# 1-Schematic_ESP32_expandable_board.net
KiCad netlist of a schematic drawn in EasyEDA
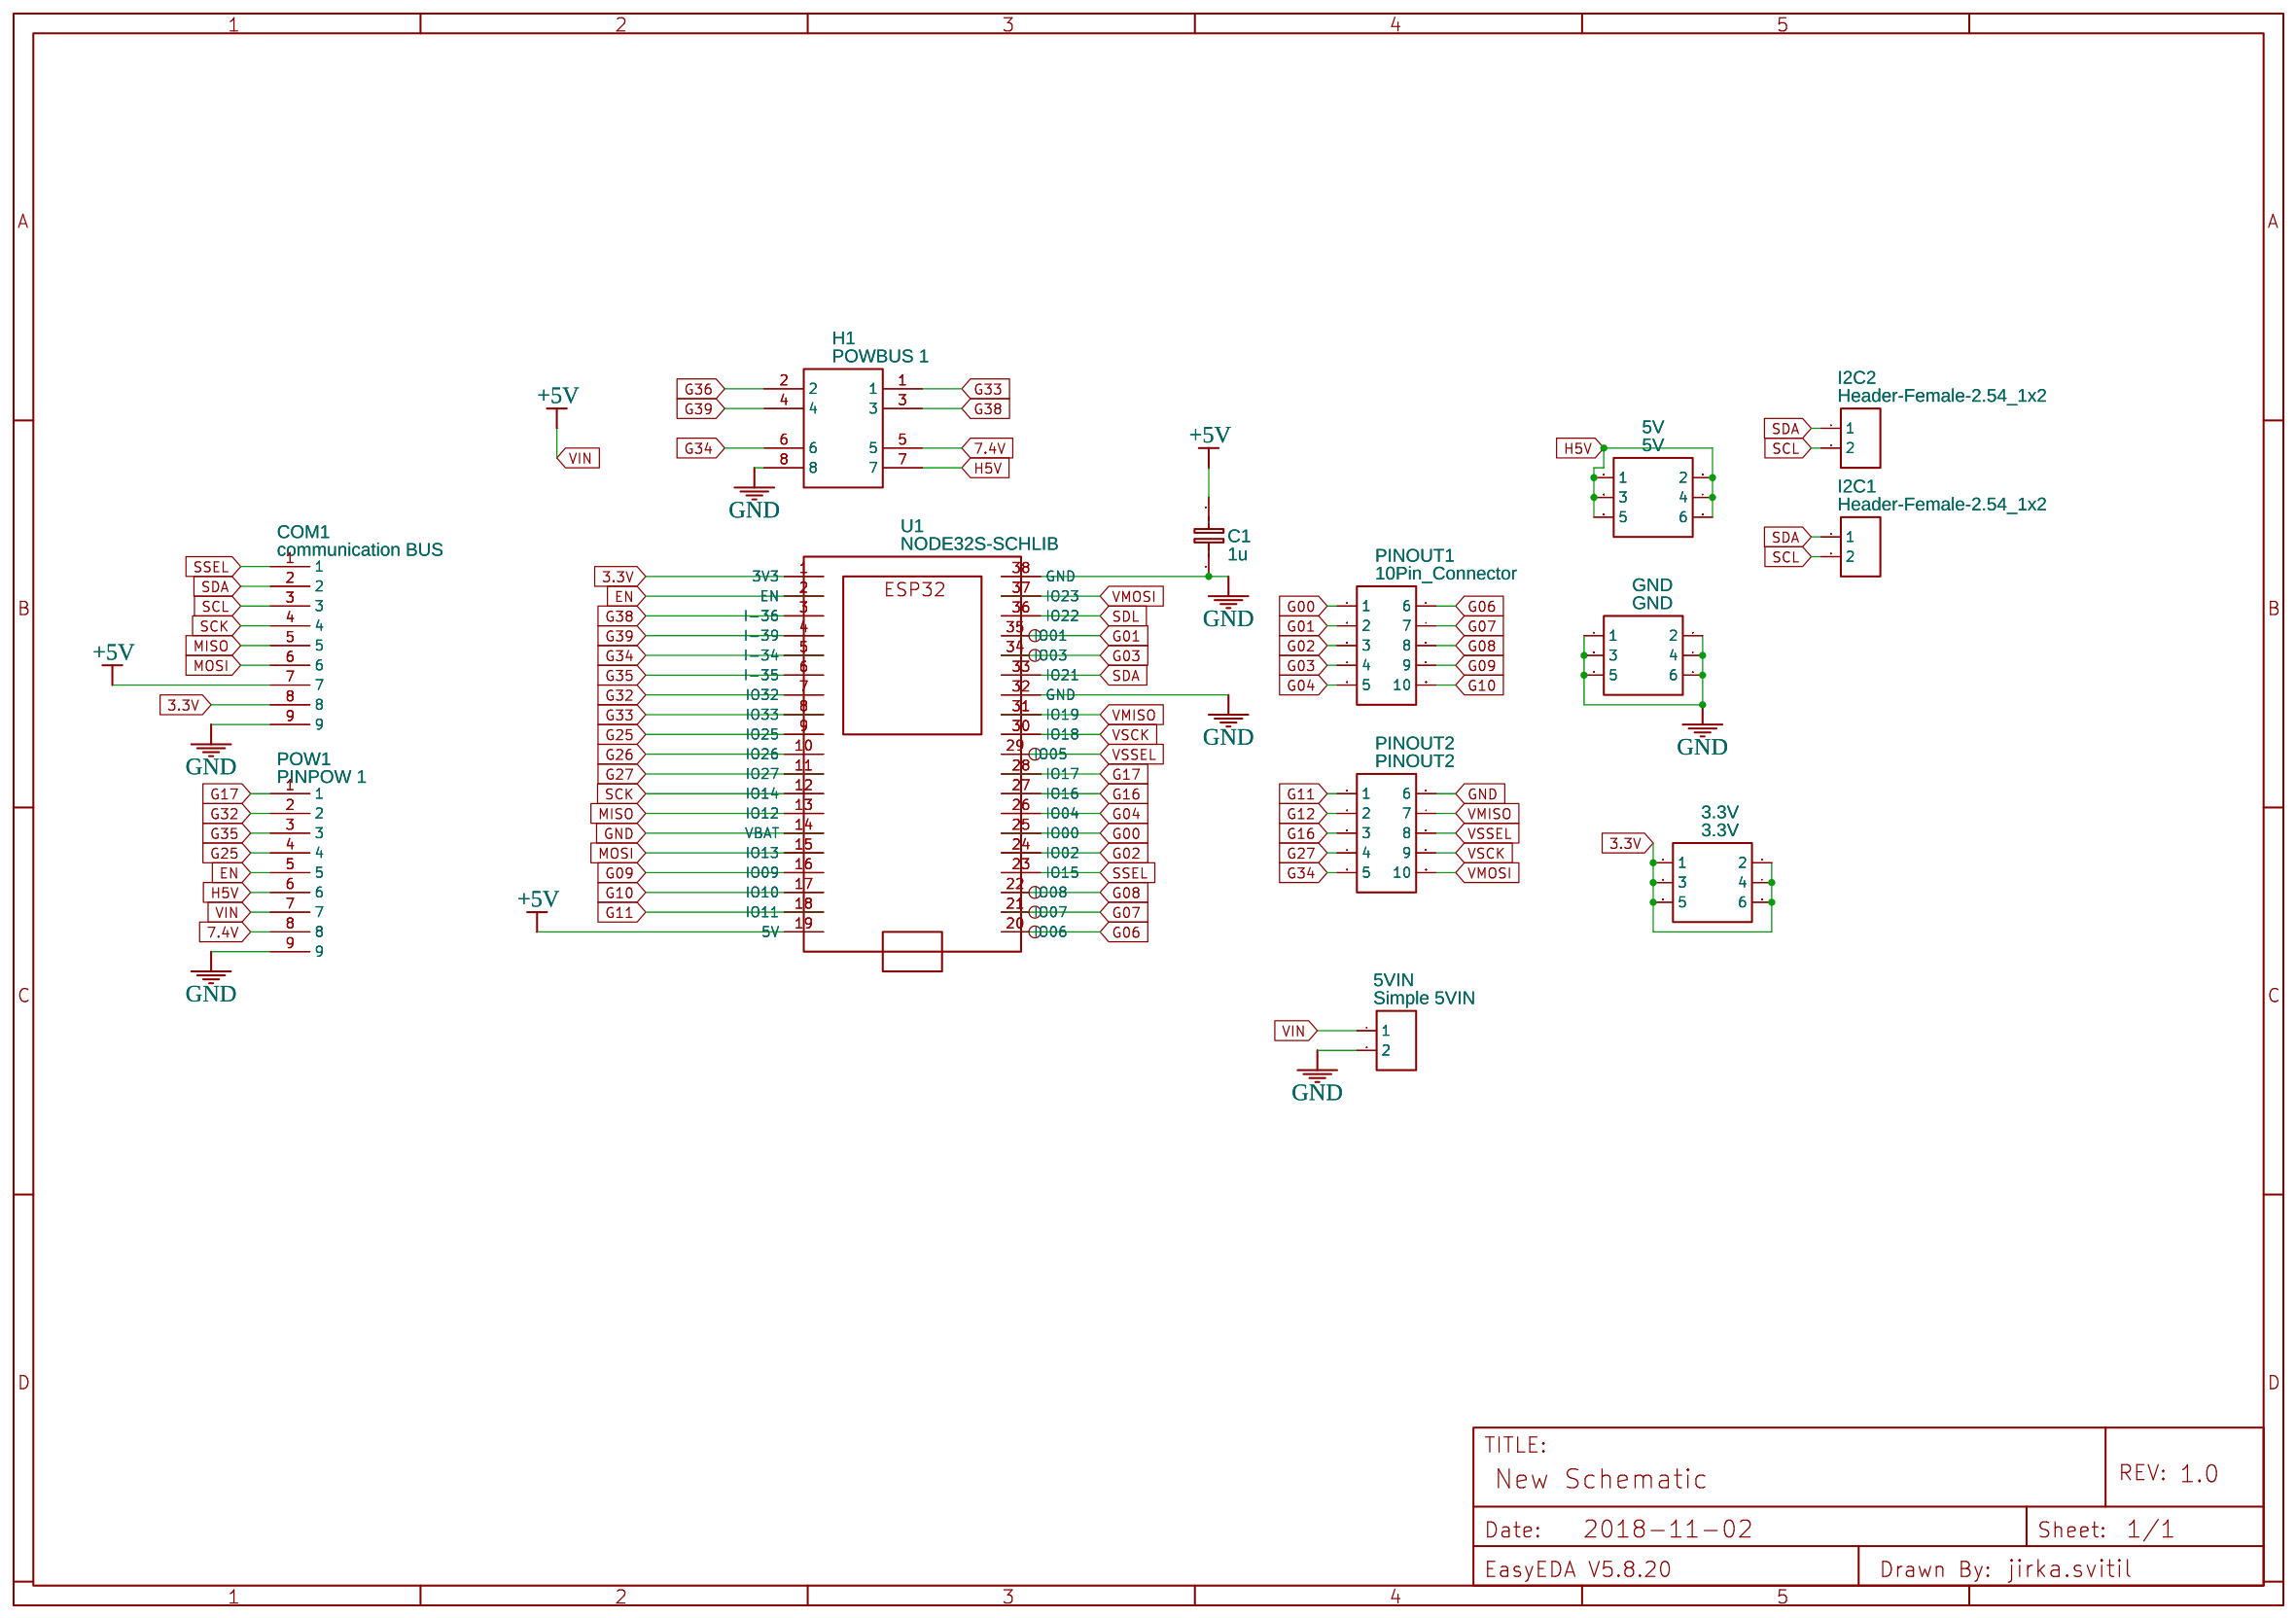
[diagram p0: schematic sheet]

(export (version "E")
  (design (tool "Eeschema 10.0.6"))
  (components
    (comp (ref "3.3V")
      (value "3.3V")
      (fields
        (field (name "BOM_Manufacturer Part") "2X3 2.54mm IDC Box")
        (field (name "BOM_Supplier Part") "C11214")
      )
      (libsource (lib "") (part "Unknown_860_440"))
    )
    (comp (ref "5V")
      (value "5V")
      (fields
        (field (name "BOM_Manufacturer Part") "2X3 2.54mm IDC Box")
        (field (name "BOM_Supplier Part") "C11214")
      )
      (libsource (lib "") (part "Unknown_830_245"))
    )
    (comp (ref "5VIN")
      (value "Simple 5VIN")
      (fields
        (field (name "BOM_Manufacturer Part") "2.54-1*2PFemale")
        (field (name "BOM_Supplier Part") "C49661")
      )
      (libsource (lib "") (part "Unknown_695_520"))
    )
    (comp (ref "C1")
      (value "1u")
      (fields (field (name "BOM_Manufacturer Part") "?"))
      (libsource (lib "") (part "Cap_RAD-0.1_EU"))
    )
    (comp (ref "COM1")
      (value "communication BUS")
      (fields (field (name "BOM_Manufacturer Part") "?"))
      (libsource (lib "") (part "Unknown_160_270"))
    )
    (comp (ref "GND")
      (value "GND")
      (fields
        (field (name "BOM_Manufacturer Part") "2X3 2.54mm IDC Box")
        (field (name "BOM_Supplier Part") "C11214")
      )
      (libsource (lib "") (part "Unknown_825_325"))
    )
    (comp (ref "H1")
      (value "POWBUS 1")
      (fields (field (name "BOM_Manufacturer Part") "Header 4x2"))
      (libsource (lib "") (part "Unknown_420_210"))
    )
    (comp (ref "I2C1")
      (value "Header-Female-2.54_1x2")
      (fields
        (field (name "BOM_Manufacturer Part") "2.54-1*2PFemale")
        (field (name "BOM_Supplier Part") "C49661")
      )
      (libsource (lib "") (part "Unknown_930_270"))
    )
    (comp (ref "I2C2")
      (value "Header-Female-2.54_1x2")
      (fields
        (field (name "BOM_Manufacturer Part") "2.54-1*2PFemale")
        (field (name "BOM_Supplier Part") "C49661")
      )
      (libsource (lib "") (part "Unknown_930_215"))
    )
    (comp (ref "PINOUT1")
      (value "10Pin_Connector")
      (fields (field (name "BOM_Manufacturer Part") "?"))
      (libsource (lib "") (part "Unknown_670_290"))
    )
    (comp (ref "PINOUT2")
      (value "PINOUT2")
      (fields (field (name "BOM_Manufacturer Part") "?"))
      (libsource (lib "") (part "Unknown_670_385"))
    )
    (comp (ref "POW1")
      (value "PINPOW 1")
      (fields (field (name "BOM_Manufacturer Part") "?"))
      (libsource (lib "") (part "Unknown_160_385"))
    )
    (comp (ref "U1")
      (value "NODE32S-SCHLIB")
      (fields (field (name "BOM_Manufacturer Part") "New SchematicLib"))
      (libsource (lib "") (part "Unknown_400_275"))
    )
  )
  (nets
    (net (code "1") (name "3.3V") (class "Default")
      (node (ref "3.3V") (pin "1") (pinfunction "1_1") (pintype "unspecified"))
      (node (ref "3.3V") (pin "2") (pinfunction "2_2") (pintype "unspecified"))
      (node (ref "3.3V") (pin "3") (pinfunction "3_3") (pintype "unspecified"))
      (node (ref "3.3V") (pin "4") (pinfunction "4_4") (pintype "unspecified"))
      (node (ref "3.3V") (pin "5") (pinfunction "5_5") (pintype "unspecified"))
      (node (ref "3.3V") (pin "6") (pinfunction "6_6") (pintype "unspecified"))
      (node (ref "COM1") (pin "8") (pinfunction "8_8") (pintype "unspecified"))
      (node (ref "U1") (pin "1") (pinfunction "3V3_1") (pintype "unspecified"))
    )
    (net (code "2") (name "7.4V") (class "Default")
      (node (ref "H1") (pin "5") (pinfunction "5_5") (pintype "unspecified"))
      (node (ref "POW1") (pin "8") (pinfunction "8_8") (pintype "unspecified"))
    )
    (net (code "3") (name "EN") (class "Default")
      (node (ref "POW1") (pin "5") (pinfunction "5_5") (pintype "unspecified"))
      (node (ref "U1") (pin "2") (pinfunction "EN_2") (pintype "unspecified"))
    )
    (net (code "4") (name "G00") (class "Default")
      (node (ref "PINOUT1") (pin "1") (pinfunction "1_1") (pintype "unspecified"))
      (node (ref "U1") (pin "25") (pinfunction "IO00_25") (pintype "unspecified"))
    )
    (net (code "5") (name "G01") (class "Default")
      (node (ref "PINOUT1") (pin "2") (pinfunction "2_2") (pintype "unspecified"))
      (node (ref "U1") (pin "35") (pinfunction "IO01_35") (pintype "unspecified"))
    )
    (net (code "6") (name "G02") (class "Default")
      (node (ref "PINOUT1") (pin "3") (pinfunction "3_3") (pintype "unspecified"))
      (node (ref "U1") (pin "24") (pinfunction "IO02_24") (pintype "unspecified"))
    )
    (net (code "7") (name "G03") (class "Default")
      (node (ref "PINOUT1") (pin "4") (pinfunction "4_4") (pintype "unspecified"))
      (node (ref "U1") (pin "34") (pinfunction "IO03_34") (pintype "unspecified"))
    )
    (net (code "8") (name "G04") (class "Default")
      (node (ref "PINOUT1") (pin "5") (pinfunction "5_5") (pintype "unspecified"))
      (node (ref "U1") (pin "26") (pinfunction "IO04_26") (pintype "unspecified"))
    )
    (net (code "9") (name "G06") (class "Default")
      (node (ref "PINOUT1") (pin "6") (pinfunction "6_6") (pintype "unspecified"))
      (node (ref "U1") (pin "20") (pinfunction "IO06_20") (pintype "unspecified"))
    )
    (net (code "10") (name "G07") (class "Default")
      (node (ref "PINOUT1") (pin "7") (pinfunction "7_7") (pintype "unspecified"))
      (node (ref "U1") (pin "21") (pinfunction "IO07_21") (pintype "unspecified"))
    )
    (net (code "11") (name "G08") (class "Default")
      (node (ref "PINOUT1") (pin "8") (pinfunction "8_8") (pintype "unspecified"))
      (node (ref "U1") (pin "22") (pinfunction "IO08_22") (pintype "unspecified"))
    )
    (net (code "12") (name "G09") (class "Default")
      (node (ref "PINOUT1") (pin "9") (pinfunction "9_9") (pintype "unspecified"))
      (node (ref "U1") (pin "16") (pinfunction "IO09_16") (pintype "unspecified"))
    )
    (net (code "13") (name "G10") (class "Default")
      (node (ref "PINOUT1") (pin "10") (pinfunction "10_10") (pintype "unspecified"))
      (node (ref "U1") (pin "17") (pinfunction "IO10_17") (pintype "unspecified"))
    )
    (net (code "14") (name "G11") (class "Default")
      (node (ref "PINOUT2") (pin "1") (pinfunction "1_1") (pintype "unspecified"))
      (node (ref "U1") (pin "18") (pinfunction "IO11_18") (pintype "unspecified"))
    )
    (net (code "15") (name "G12") (class "Default")
      (node (ref "PINOUT2") (pin "2") (pinfunction "2_2") (pintype "unspecified"))
    )
    (net (code "16") (name "G16") (class "Default")
      (node (ref "PINOUT2") (pin "3") (pinfunction "3_3") (pintype "unspecified"))
      (node (ref "U1") (pin "27") (pinfunction "IO16_27") (pintype "unspecified"))
    )
    (net (code "17") (name "G17") (class "Default")
      (node (ref "POW1") (pin "1") (pinfunction "1_1") (pintype "unspecified"))
      (node (ref "U1") (pin "28") (pinfunction "IO17_28") (pintype "unspecified"))
    )
    (net (code "18") (name "G25") (class "Default")
      (node (ref "POW1") (pin "4") (pinfunction "4_4") (pintype "unspecified"))
      (node (ref "U1") (pin "9") (pinfunction "IO25_9") (pintype "unspecified"))
    )
    (net (code "19") (name "G26") (class "Default")
      (node (ref "U1") (pin "10") (pinfunction "IO26_10") (pintype "unspecified"))
    )
    (net (code "20") (name "G27") (class "Default")
      (node (ref "PINOUT2") (pin "4") (pinfunction "4_4") (pintype "unspecified"))
      (node (ref "U1") (pin "11") (pinfunction "IO27_11") (pintype "unspecified"))
    )
    (net (code "21") (name "G32") (class "Default")
      (node (ref "POW1") (pin "2") (pinfunction "2_2") (pintype "unspecified"))
      (node (ref "U1") (pin "7") (pinfunction "IO32_7") (pintype "unspecified"))
    )
    (net (code "22") (name "G33") (class "Default")
      (node (ref "H1") (pin "1") (pinfunction "1_1") (pintype "unspecified"))
      (node (ref "U1") (pin "8") (pinfunction "IO33_8") (pintype "unspecified"))
    )
    (net (code "23") (name "G34") (class "Default")
      (node (ref "H1") (pin "6") (pinfunction "6_6") (pintype "unspecified"))
      (node (ref "PINOUT2") (pin "5") (pinfunction "5_5") (pintype "unspecified"))
      (node (ref "U1") (pin "5") (pinfunction "I-34_5") (pintype "unspecified"))
    )
    (net (code "24") (name "G35") (class "Default")
      (node (ref "POW1") (pin "3") (pinfunction "3_3") (pintype "unspecified"))
      (node (ref "U1") (pin "6") (pinfunction "I-35_6") (pintype "unspecified"))
    )
    (net (code "25") (name "G36") (class "Default")
      (node (ref "H1") (pin "2") (pinfunction "2_2") (pintype "unspecified"))
    )
    (net (code "26") (name "G38") (class "Default")
      (node (ref "H1") (pin "3") (pinfunction "3_3") (pintype "unspecified"))
      (node (ref "U1") (pin "3") (pinfunction "I-36_3") (pintype "unspecified"))
    )
    (net (code "27") (name "G39") (class "Default")
      (node (ref "H1") (pin "4") (pinfunction "4_4") (pintype "unspecified"))
      (node (ref "U1") (pin "4") (pinfunction "I-39_4") (pintype "unspecified"))
    )
    (net (code "28") (name "GND") (class "Default")
      (node (ref "5VIN") (pin "2") (pinfunction "2_2") (pintype "input"))
      (node (ref "C1") (pin "2") (pinfunction "2_2") (pintype "unspecified"))
      (node (ref "COM1") (pin "9") (pinfunction "9_9") (pintype "unspecified"))
      (node (ref "GND") (pin "1") (pinfunction "1_1") (pintype "unspecified"))
      (node (ref "GND") (pin "2") (pinfunction "2_2") (pintype "unspecified"))
      (node (ref "GND") (pin "3") (pinfunction "3_3") (pintype "unspecified"))
      (node (ref "GND") (pin "4") (pinfunction "4_4") (pintype "unspecified"))
      (node (ref "GND") (pin "5") (pinfunction "5_5") (pintype "unspecified"))
      (node (ref "GND") (pin "6") (pinfunction "6_6") (pintype "unspecified"))
      (node (ref "H1") (pin "8") (pinfunction "8_8") (pintype "unspecified"))
      (node (ref "PINOUT2") (pin "6") (pinfunction "6_6") (pintype "unspecified"))
      (node (ref "POW1") (pin "9") (pinfunction "9_9") (pintype "unspecified"))
      (node (ref "U1") (pin "14") (pinfunction "VBAT_14") (pintype "unspecified"))
      (node (ref "U1") (pin "32") (pinfunction "GND_32") (pintype "unspecified"))
      (node (ref "U1") (pin "38") (pinfunction "GND_38") (pintype "passive"))
    )
    (net (code "29") (name "H5V") (class "Default")
      (node (ref "5V") (pin "1") (pinfunction "1_1") (pintype "unspecified"))
      (node (ref "5V") (pin "2") (pinfunction "2_2") (pintype "unspecified"))
      (node (ref "5V") (pin "3") (pinfunction "3_3") (pintype "unspecified"))
      (node (ref "5V") (pin "4") (pinfunction "4_4") (pintype "unspecified"))
      (node (ref "5V") (pin "5") (pinfunction "5_5") (pintype "unspecified"))
      (node (ref "5V") (pin "6") (pinfunction "6_6") (pintype "unspecified"))
      (node (ref "H1") (pin "7") (pinfunction "7_7") (pintype "unspecified"))
      (node (ref "POW1") (pin "6") (pinfunction "6_6") (pintype "unspecified"))
    )
    (net (code "30") (name "MISO") (class "Default")
      (node (ref "COM1") (pin "5") (pinfunction "5_5") (pintype "unspecified"))
      (node (ref "U1") (pin "13") (pinfunction "IO12_13") (pintype "unspecified"))
    )
    (net (code "31") (name "MOSI") (class "Default")
      (node (ref "COM1") (pin "6") (pinfunction "6_6") (pintype "unspecified"))
      (node (ref "U1") (pin "15") (pinfunction "IO13_15") (pintype "unspecified"))
    )
    (net (code "32") (name "SCK") (class "Default")
      (node (ref "COM1") (pin "4") (pinfunction "4_4") (pintype "unspecified"))
      (node (ref "U1") (pin "12") (pinfunction "IO14_12") (pintype "unspecified"))
    )
    (net (code "33") (name "SCL") (class "Default")
      (node (ref "COM1") (pin "3") (pinfunction "3_3") (pintype "unspecified"))
      (node (ref "I2C1") (pin "2") (pinfunction "2_2") (pintype "input"))
      (node (ref "I2C2") (pin "2") (pinfunction "2_2") (pintype "input"))
    )
    (net (code "34") (name "SDA") (class "Default")
      (node (ref "COM1") (pin "2") (pinfunction "2_2") (pintype "unspecified"))
      (node (ref "I2C1") (pin "1") (pinfunction "1_1") (pintype "input"))
      (node (ref "I2C2") (pin "1") (pinfunction "1_1") (pintype "input"))
      (node (ref "U1") (pin "33") (pinfunction "IO21_33") (pintype "unspecified"))
    )
    (net (code "35") (name "SDL") (class "Default")
      (node (ref "U1") (pin "36") (pinfunction "IO22_36") (pintype "bidirectional"))
    )
    (net (code "36") (name "SSEL") (class "Default")
      (node (ref "COM1") (pin "1") (pinfunction "1_1") (pintype "unspecified"))
      (node (ref "U1") (pin "23") (pinfunction "IO15_23") (pintype "unspecified"))
    )
    (net (code "37") (name "VIN") (class "Default")
      (node (ref "5VIN") (pin "1") (pinfunction "1_1") (pintype "input"))
      (node (ref "C1") (pin "1") (pinfunction "1_1") (pintype "unspecified"))
      (node (ref "COM1") (pin "7") (pinfunction "7_7") (pintype "unspecified"))
      (node (ref "POW1") (pin "7") (pinfunction "7_7") (pintype "unspecified"))
      (node (ref "U1") (pin "19") (pinfunction "5V_19") (pintype "unspecified"))
    )
    (net (code "38") (name "VMISO") (class "Default")
      (node (ref "PINOUT2") (pin "7") (pinfunction "7_7") (pintype "unspecified"))
      (node (ref "U1") (pin "31") (pinfunction "IO19_31") (pintype "unspecified"))
    )
    (net (code "39") (name "VMOSI") (class "Default")
      (node (ref "PINOUT2") (pin "10") (pinfunction "10_10") (pintype "unspecified"))
      (node (ref "U1") (pin "37") (pinfunction "IO23_37") (pintype "bidirectional"))
    )
    (net (code "40") (name "VSCK") (class "Default")
      (node (ref "PINOUT2") (pin "9") (pinfunction "9_9") (pintype "unspecified"))
      (node (ref "U1") (pin "30") (pinfunction "IO18_30") (pintype "unspecified"))
    )
    (net (code "41") (name "VSSEL") (class "Default")
      (node (ref "PINOUT2") (pin "8") (pinfunction "8_8") (pintype "unspecified"))
      (node (ref "U1") (pin "29") (pinfunction "IO05_29") (pintype "unspecified"))
    )
  )
)
